# Communication_with_IO.net
KiCad netlist of a schematic drawn in Altium Designer
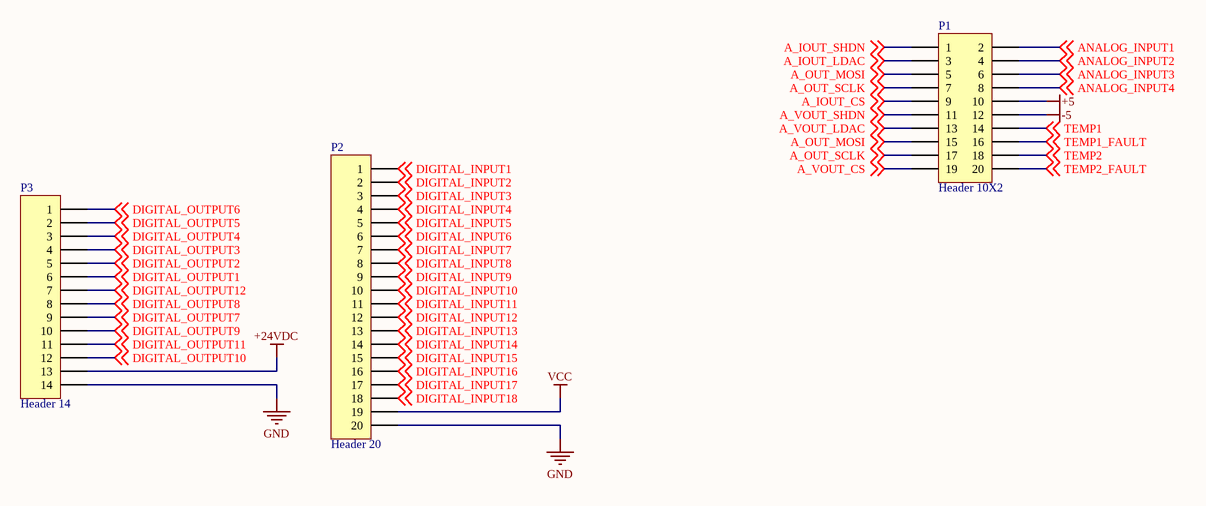
[diagram p0: Communication_with_IO.SchDoc]

(export (version "E")
  (design (tool "Eeschema 10.0.6"))
  (components
    (comp (ref "P1")
      (value "Header 10X2")
      (footprint "HDR2X10")
      (description "Header, 10-Pin, Dual row")
      (fields (field (name "PUBLISHER") "Altium Limited"))
      (libsource (lib "Miscellaneous Connectors") (part "Header 10X2"))
    )
    (comp (ref "P2")
      (value "Header 20")
      (footprint "HDR1X20")
      (description "Header, 20-Pin")
      (fields (field (name "PUBLISHER") "Altium Limited"))
      (libsource (lib "Miscellaneous Connectors") (part "Header 20"))
    )
    (comp (ref "P3")
      (value "Header 14")
      (footprint "HDR1X14")
      (description "Header, 14-Pin")
      (fields (field (name "PUBLISHER") "Altium Limited"))
      (libsource (lib "Miscellaneous Connectors") (part "Header 14"))
    )
  )
  (nets
    (net (code "1") (name "+5") (class "Default")
      (node (ref "P1") (pin "10") (pinfunction "10_10") (pintype "passive"))
    )
    (net (code "2") (name "+24VDC") (class "Default")
      (node (ref "P3") (pin "13") (pinfunction "13_13") (pintype "passive"))
    )
    (net (code "3") (name "-5") (class "Default")
      (node (ref "P1") (pin "12") (pinfunction "12_12") (pintype "passive"))
    )
    (net (code "4") (name "ANALOG_INPUT1") (class "Default")
      (node (ref "P1") (pin "2") (pinfunction "2_2") (pintype "passive"))
    )
    (net (code "5") (name "ANALOG_INPUT2") (class "Default")
      (node (ref "P1") (pin "4") (pinfunction "4_4") (pintype "passive"))
    )
    (net (code "6") (name "ANALOG_INPUT3") (class "Default")
      (node (ref "P1") (pin "6") (pinfunction "6_6") (pintype "passive"))
    )
    (net (code "7") (name "ANALOG_INPUT4") (class "Default")
      (node (ref "P1") (pin "8") (pinfunction "8_8") (pintype "passive"))
    )
    (net (code "8") (name "A_IOUT_CS") (class "Default")
      (node (ref "P1") (pin "9") (pinfunction "9_9") (pintype "passive"))
    )
    (net (code "9") (name "A_IOUT_LDAC") (class "Default")
      (node (ref "P1") (pin "3") (pinfunction "3_3") (pintype "passive"))
    )
    (net (code "10") (name "A_IOUT_SHDN") (class "Default")
      (node (ref "P1") (pin "1") (pinfunction "1_1") (pintype "passive"))
    )
    (net (code "11") (name "A_OUT_MOSI") (class "Default")
      (node (ref "P1") (pin "15") (pinfunction "15_15") (pintype "passive"))
      (node (ref "P1") (pin "5") (pinfunction "5_5") (pintype "passive"))
    )
    (net (code "12") (name "A_OUT_SCLK") (class "Default")
      (node (ref "P1") (pin "17") (pinfunction "17_17") (pintype "passive"))
      (node (ref "P1") (pin "7") (pinfunction "7_7") (pintype "passive"))
    )
    (net (code "13") (name "A_VOUT_CS") (class "Default")
      (node (ref "P1") (pin "19") (pinfunction "19_19") (pintype "passive"))
    )
    (net (code "14") (name "A_VOUT_LDAC") (class "Default")
      (node (ref "P1") (pin "13") (pinfunction "13_13") (pintype "passive"))
    )
    (net (code "15") (name "A_VOUT_SHDN") (class "Default")
      (node (ref "P1") (pin "11") (pinfunction "11_11") (pintype "passive"))
    )
    (net (code "16") (name "DIGITAL_INPUT1") (class "Default")
      (node (ref "P2") (pin "1") (pinfunction "1_1") (pintype "passive"))
    )
    (net (code "17") (name "DIGITAL_INPUT2") (class "Default")
      (node (ref "P2") (pin "2") (pinfunction "2_2") (pintype "passive"))
    )
    (net (code "18") (name "DIGITAL_INPUT3") (class "Default")
      (node (ref "P2") (pin "3") (pinfunction "3_3") (pintype "passive"))
    )
    (net (code "19") (name "DIGITAL_INPUT4") (class "Default")
      (node (ref "P2") (pin "4") (pinfunction "4_4") (pintype "passive"))
    )
    (net (code "20") (name "DIGITAL_INPUT5") (class "Default")
      (node (ref "P2") (pin "5") (pinfunction "5_5") (pintype "passive"))
    )
    (net (code "21") (name "DIGITAL_INPUT6") (class "Default")
      (node (ref "P2") (pin "6") (pinfunction "6_6") (pintype "passive"))
    )
    (net (code "22") (name "DIGITAL_INPUT7") (class "Default")
      (node (ref "P2") (pin "7") (pinfunction "7_7") (pintype "passive"))
    )
    (net (code "23") (name "DIGITAL_INPUT8") (class "Default")
      (node (ref "P2") (pin "8") (pinfunction "8_8") (pintype "passive"))
    )
    (net (code "24") (name "DIGITAL_INPUT9") (class "Default")
      (node (ref "P2") (pin "9") (pinfunction "9_9") (pintype "passive"))
    )
    (net (code "25") (name "DIGITAL_INPUT10") (class "Default")
      (node (ref "P2") (pin "10") (pinfunction "10_10") (pintype "passive"))
    )
    (net (code "26") (name "DIGITAL_INPUT11") (class "Default")
      (node (ref "P2") (pin "11") (pinfunction "11_11") (pintype "passive"))
    )
    (net (code "27") (name "DIGITAL_INPUT12") (class "Default")
      (node (ref "P2") (pin "12") (pinfunction "12_12") (pintype "passive"))
    )
    (net (code "28") (name "DIGITAL_INPUT13") (class "Default")
      (node (ref "P2") (pin "13") (pinfunction "13_13") (pintype "passive"))
    )
    (net (code "29") (name "DIGITAL_INPUT14") (class "Default")
      (node (ref "P2") (pin "14") (pinfunction "14_14") (pintype "passive"))
    )
    (net (code "30") (name "DIGITAL_INPUT15") (class "Default")
      (node (ref "P2") (pin "15") (pinfunction "15_15") (pintype "passive"))
    )
    (net (code "31") (name "DIGITAL_INPUT16") (class "Default")
      (node (ref "P2") (pin "16") (pinfunction "16_16") (pintype "passive"))
    )
    (net (code "32") (name "DIGITAL_INPUT17") (class "Default")
      (node (ref "P2") (pin "17") (pinfunction "17_17") (pintype "passive"))
    )
    (net (code "33") (name "DIGITAL_INPUT18") (class "Default")
      (node (ref "P2") (pin "18") (pinfunction "18_18") (pintype "passive"))
    )
    (net (code "34") (name "DIGITAL_OUTPUT1") (class "Default")
      (node (ref "P3") (pin "6") (pinfunction "6_6") (pintype "passive"))
    )
    (net (code "35") (name "DIGITAL_OUTPUT2") (class "Default")
      (node (ref "P3") (pin "5") (pinfunction "5_5") (pintype "passive"))
    )
    (net (code "36") (name "DIGITAL_OUTPUT3") (class "Default")
      (node (ref "P3") (pin "4") (pinfunction "4_4") (pintype "passive"))
    )
    (net (code "37") (name "DIGITAL_OUTPUT4") (class "Default")
      (node (ref "P3") (pin "3") (pinfunction "3_3") (pintype "passive"))
    )
    (net (code "38") (name "DIGITAL_OUTPUT5") (class "Default")
      (node (ref "P3") (pin "2") (pinfunction "2_2") (pintype "passive"))
    )
    (net (code "39") (name "DIGITAL_OUTPUT6") (class "Default")
      (node (ref "P3") (pin "1") (pinfunction "1_1") (pintype "passive"))
    )
    (net (code "40") (name "DIGITAL_OUTPUT7") (class "Default")
      (node (ref "P3") (pin "9") (pinfunction "9_9") (pintype "passive"))
    )
    (net (code "41") (name "DIGITAL_OUTPUT8") (class "Default")
      (node (ref "P3") (pin "8") (pinfunction "8_8") (pintype "passive"))
    )
    (net (code "42") (name "DIGITAL_OUTPUT9") (class "Default")
      (node (ref "P3") (pin "10") (pinfunction "10_10") (pintype "passive"))
    )
    (net (code "43") (name "DIGITAL_OUTPUT10") (class "Default")
      (node (ref "P3") (pin "12") (pinfunction "12_12") (pintype "passive"))
    )
    (net (code "44") (name "DIGITAL_OUTPUT11") (class "Default")
      (node (ref "P3") (pin "11") (pinfunction "11_11") (pintype "passive"))
    )
    (net (code "45") (name "DIGITAL_OUTPUT12") (class "Default")
      (node (ref "P3") (pin "7") (pinfunction "7_7") (pintype "passive"))
    )
    (net (code "46") (name "GND") (class "Default")
      (node (ref "P2") (pin "20") (pinfunction "20_20") (pintype "passive"))
      (node (ref "P3") (pin "14") (pinfunction "14_14") (pintype "passive"))
    )
    (net (code "47") (name "TEMP1") (class "Default")
      (node (ref "P1") (pin "14") (pinfunction "14_14") (pintype "passive"))
    )
    (net (code "48") (name "TEMP1_FAULT") (class "Default")
      (node (ref "P1") (pin "16") (pinfunction "16_16") (pintype "passive"))
    )
    (net (code "49") (name "TEMP2") (class "Default")
      (node (ref "P1") (pin "18") (pinfunction "18_18") (pintype "passive"))
    )
    (net (code "50") (name "TEMP2_FAULT") (class "Default")
      (node (ref "P1") (pin "20") (pinfunction "20_20") (pintype "passive"))
    )
    (net (code "51") (name "VCC") (class "Default")
      (node (ref "P2") (pin "19") (pinfunction "19_19") (pintype "passive"))
    )
  )
)
